# NE555_dutycycle.net
KiCad netlist of a schematic drawn in EasyEDA
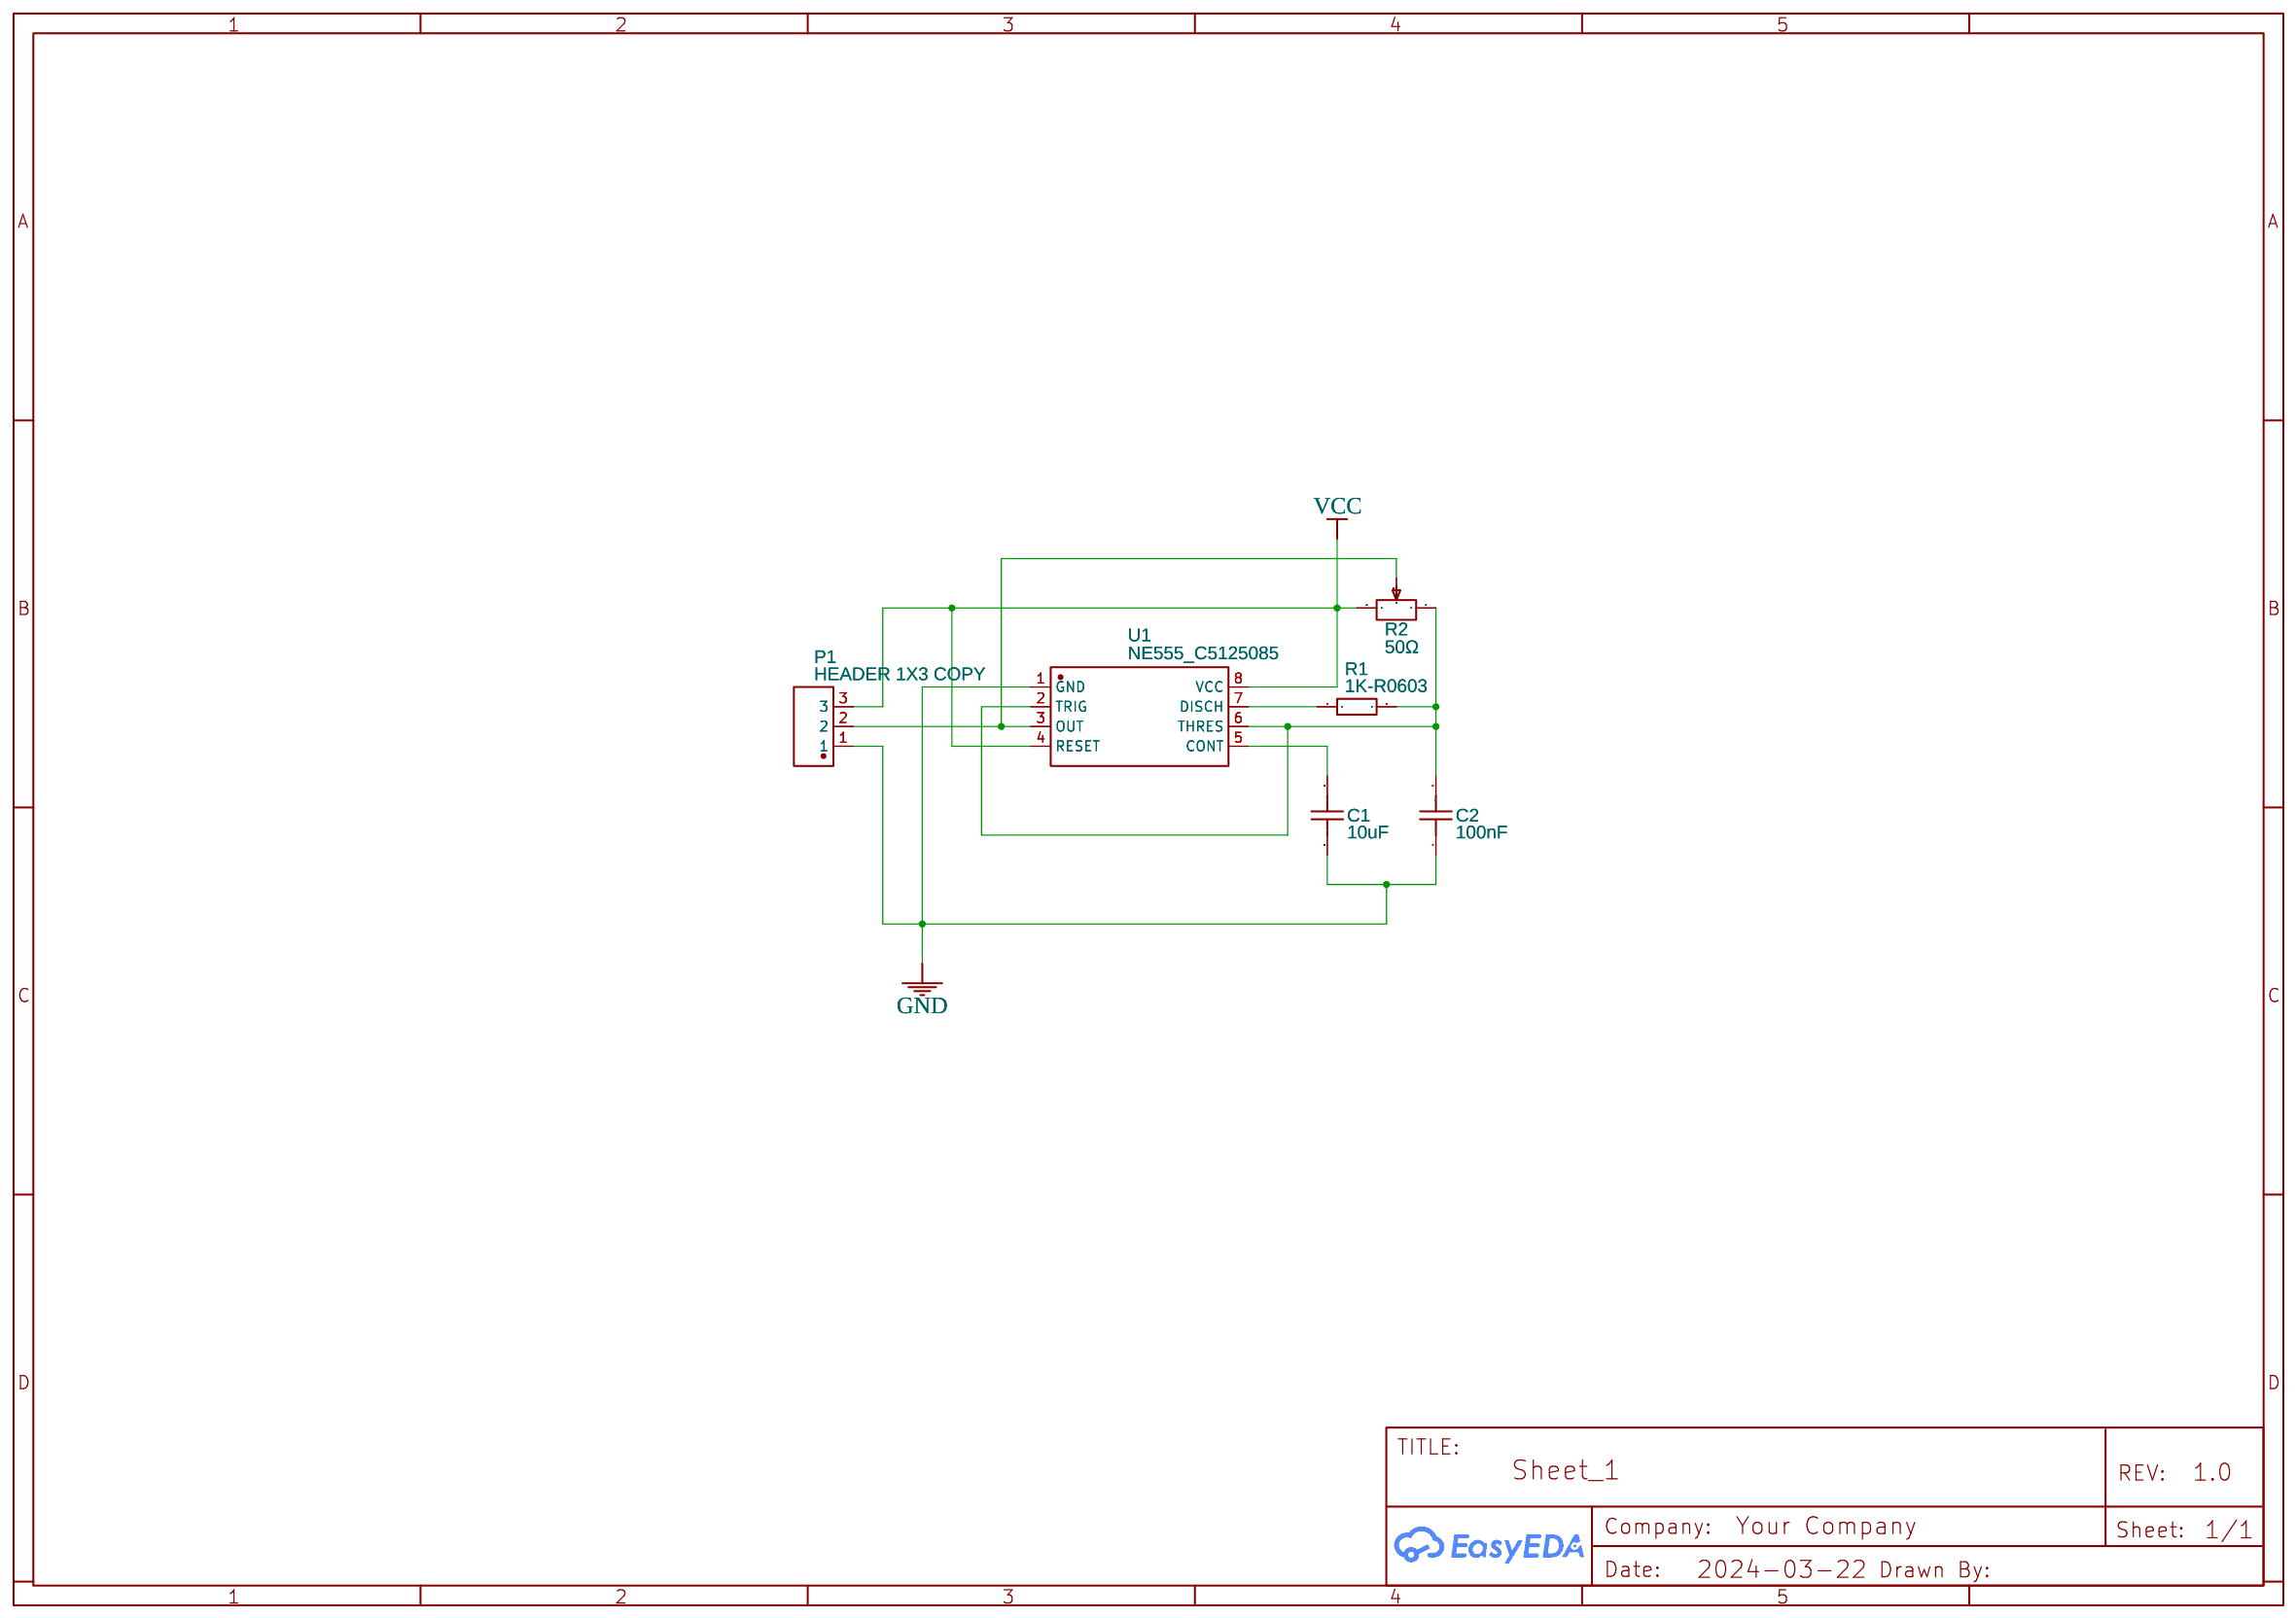
[diagram p0: schematic sheet]

(export (version "E")
  (design (tool "Eeschema 10.0.6"))
  (components
    (comp (ref "C1") (value "10uF") (libsource (lib "") (part "C_0603_US")))
    (comp (ref "C2") (value "100nF") (libsource (lib "") (part "C_0603_US")))
    (comp (ref "P1")
      (value "HEADER 1X3 COPY")
      (fields (field (name "Manufacturer Part") "M3025V-1x6P") (field (name "Manufacturer") "XFCN"))
      (libsource (lib "") (part "HEADER 1X3 COPY"))
    )
    (comp (ref "R1") (value "1K-R0603") (libsource (lib "") (part "1K-R0603")))
    (comp (ref "R2")
      (value "50Ω")
      (fields
        (field (name "Manufacturer Part") "Precision potentiometer 3296W/50ohm")
        (field (name "Manufacturer") "ReliaPro")
      )
      (libsource (lib "") (part "Precision potentiometer 3296W/50ohm"))
    )
    (comp (ref "U1")
      (value "NE555_C5125085")
      (fields (field (name "Manufacturer Part") "NE555") (field (name "Manufacturer") "IDCHIP(英锐芯)"))
      (libsource (lib "") (part "NE555_C5125085"))
    )
  )
  (nets
    (net (code "1") (name "GND") (class "Default")
      (node (ref "C1") (pin "1") (pinfunction "1_1") (pintype "unspecified"))
      (node (ref "C2") (pin "1") (pinfunction "1_1") (pintype "unspecified"))
      (node (ref "P1") (pin "1") (pinfunction "1_1") (pintype "unspecified"))
      (node (ref "U1") (pin "1") (pinfunction "GND_1") (pintype "unspecified"))
    )
    (net (code "2") (name "Net-(U1-CONT)") (class "Default")
      (node (ref "C1") (pin "2") (pinfunction "2_2") (pintype "unspecified"))
      (node (ref "U1") (pin "5") (pinfunction "CONT_5") (pintype "unspecified"))
    )
    (net (code "3") (name "Net-(U1-DISCH)") (class "Default")
      (node (ref "R1") (pin "1") (pinfunction "1_1") (pintype "unspecified"))
      (node (ref "U1") (pin "7") (pinfunction "DISCH_7") (pintype "unspecified"))
    )
    (net (code "4") (name "Net-(U1-OUT)") (class "Default")
      (node (ref "P1") (pin "2") (pinfunction "2_2") (pintype "unspecified"))
      (node (ref "R2") (pin "2") (pinfunction "2_2") (pintype "input"))
      (node (ref "U1") (pin "3") (pinfunction "OUT_3") (pintype "unspecified"))
    )
    (net (code "5") (name "Net-(U1-THRES)") (class "Default")
      (node (ref "C2") (pin "2") (pinfunction "2_2") (pintype "unspecified"))
      (node (ref "R1") (pin "2") (pinfunction "2_2") (pintype "unspecified"))
      (node (ref "R2") (pin "1") (pinfunction "1_1") (pintype "input"))
      (node (ref "U1") (pin "2") (pinfunction "TRIG_2") (pintype "unspecified"))
      (node (ref "U1") (pin "6") (pinfunction "THRES_6") (pintype "unspecified"))
    )
    (net (code "6") (name "VCC") (class "Default")
      (node (ref "P1") (pin "3") (pinfunction "3_3") (pintype "unspecified"))
      (node (ref "R2") (pin "3") (pinfunction "3_3") (pintype "input"))
      (node (ref "U1") (pin "4") (pinfunction "RESET_4") (pintype "unspecified"))
      (node (ref "U1") (pin "8") (pinfunction "VCC_8") (pintype "unspecified"))
    )
  )
)
